# pump.net
KiCad netlist of a schematic drawn in Altium Designer
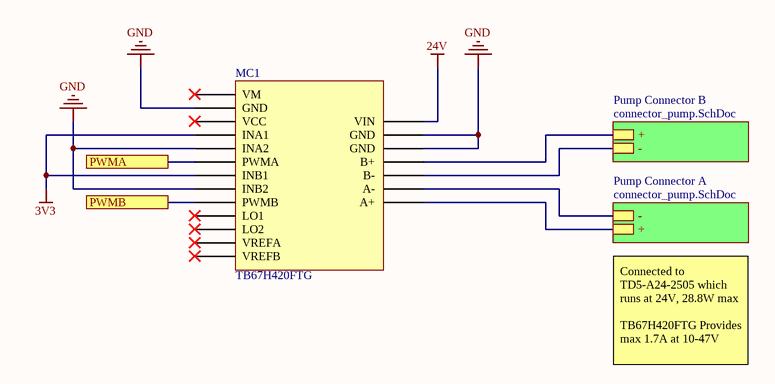
[diagram p0: pump.SchDoc]

(export (version "E")
  (design (tool "Eeschema 10.0.6"))
  (components
    (comp (ref "MC1")
      (value "TB67H420FTG")
      (footprint "TB67H420FTG Dual/Single Motor Driver Carrier")
      (libsource (lib "brew_lib") (part "TB67H420FTG Dual/Single Motor Driver Carrier"))
    )
  )
  (nets
    (net (code "1") (name "/+") (class "Default")
      (node (ref "MC1") (pin "17") (pinfunction "B+_17") (pintype "passive"))
    )
    (net (code "2") (name "/+_1") (class "Default")
      (node (ref "MC1") (pin "14") (pinfunction "A+_14") (pintype "passive"))
    )
    (net (code "3") (name "/-") (class "Default")
      (node (ref "MC1") (pin "16") (pinfunction "B-_16") (pintype "passive"))
    )
    (net (code "4") (name "/-_1") (class "Default")
      (node (ref "MC1") (pin "15") (pinfunction "A-_15") (pintype "passive"))
    )
    (net (code "5") (name "/PWMA") (class "Default")
      (node (ref "MC1") (pin "6") (pinfunction "PWMA_6") (pintype "passive"))
    )
    (net (code "6") (name "/PWMB") (class "Default")
      (node (ref "MC1") (pin "9") (pinfunction "PWMB_9") (pintype "passive"))
    )
    (net (code "7") (name "3V3") (class "Default")
      (node (ref "MC1") (pin "4") (pinfunction "INA1_4") (pintype "passive"))
      (node (ref "MC1") (pin "7") (pinfunction "INB1_7") (pintype "passive"))
    )
    (net (code "8") (name "24V") (class "Default")
      (node (ref "MC1") (pin "20") (pinfunction "VIN_20") (pintype "passive"))
    )
    (net (code "9") (name "GND") (class "Default")
      (node (ref "MC1") (pin "18") (pinfunction "GND_18") (pintype "passive"))
      (node (ref "MC1") (pin "19") (pinfunction "GND_19") (pintype "passive"))
      (node (ref "MC1") (pin "2") (pinfunction "GND_2") (pintype "passive"))
      (node (ref "MC1") (pin "5") (pinfunction "INA2_5") (pintype "passive"))
      (node (ref "MC1") (pin "8") (pinfunction "INB2_8") (pintype "passive"))
    )
    (net (code "10") (name "unconnected-(MC1-LO1-Pad10)") (class "Default")
      (node (ref "MC1") (pin "10") (pinfunction "LO1_10") (pintype "passive+no_connect"))
    )
    (net (code "11") (name "unconnected-(MC1-LO2-Pad11)") (class "Default")
      (node (ref "MC1") (pin "11") (pinfunction "LO2_11") (pintype "passive+no_connect"))
    )
    (net (code "12") (name "unconnected-(MC1-VCC-Pad3)") (class "Default")
      (node (ref "MC1") (pin "3") (pinfunction "VCC_3") (pintype "passive+no_connect"))
    )
    (net (code "13") (name "unconnected-(MC1-VM-Pad1)") (class "Default")
      (node (ref "MC1") (pin "1") (pinfunction "VM_1") (pintype "passive+no_connect"))
    )
    (net (code "14") (name "unconnected-(MC1-VREFA-Pad12)") (class "Default")
      (node (ref "MC1") (pin "12") (pinfunction "VREFA_12") (pintype "passive+no_connect"))
    )
    (net (code "15") (name "unconnected-(MC1-VREFB-Pad13)") (class "Default")
      (node (ref "MC1") (pin "13") (pinfunction "VREFB_13") (pintype "passive+no_connect"))
    )
  )
)
